# PulseGen.net
KiCad netlist of a schematic drawn in EAGLE
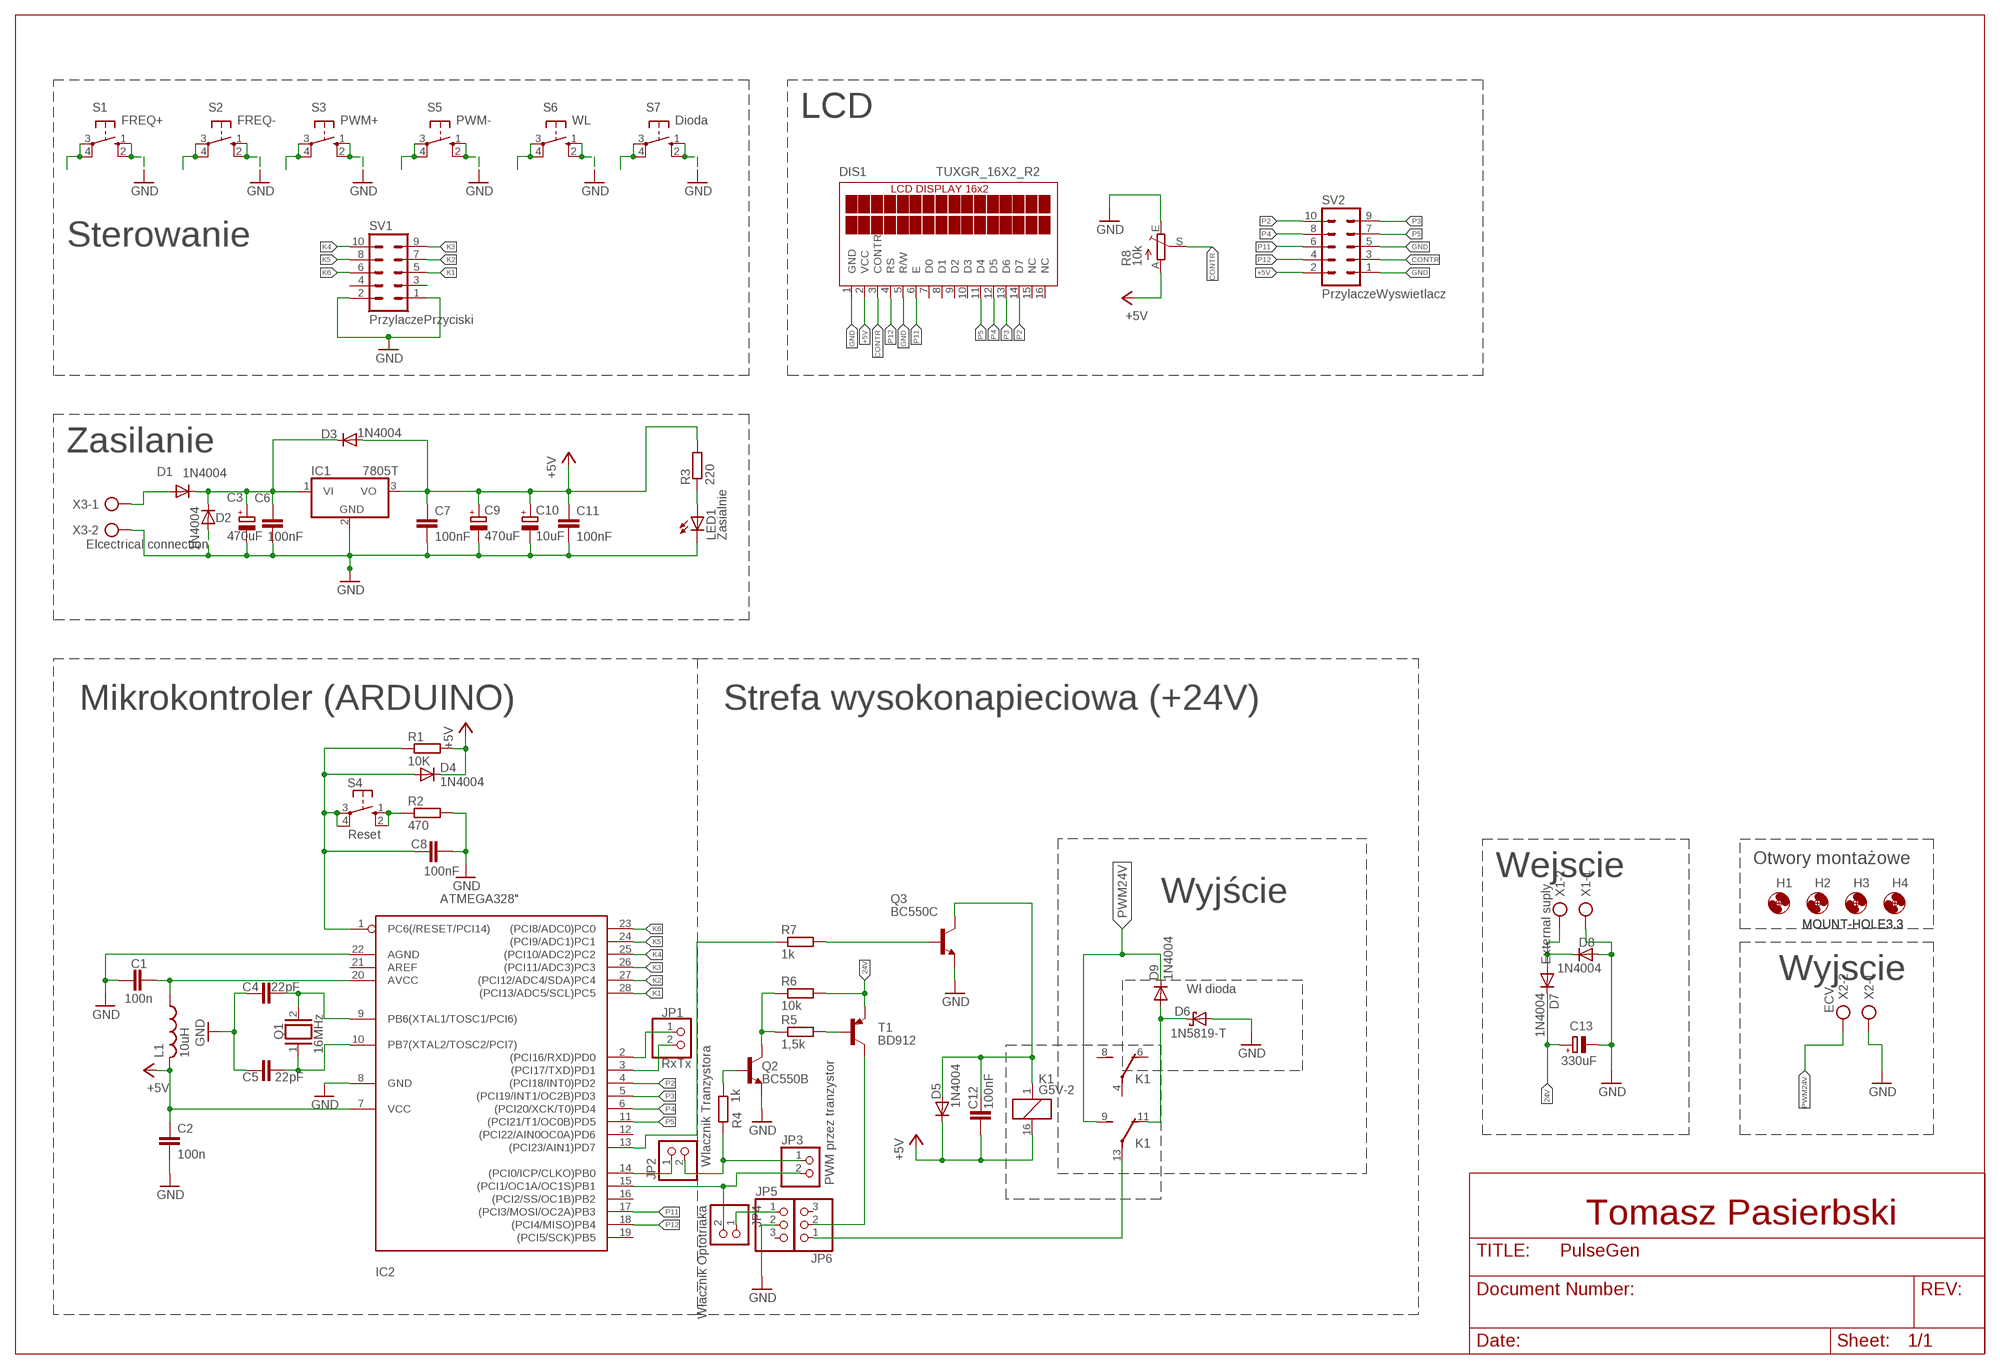
[diagram p0: schematic, sheet 1]

(export (version "E")
  (design (tool "Eeschema 10.0.6"))
  (components
    (comp (ref "C1")
      (value "100n")
      (footprint "eagle-import:C025-030X050")
      (libsource (lib "eagle-import") (part "C-EU025-030X050"))
    )
    (comp (ref "C2")
      (value "100n")
      (footprint "eagle-import:C025-030X050")
      (libsource (lib "eagle-import") (part "C-EU025-030X050"))
    )
    (comp (ref "C3")
      (value "470uF")
      (footprint "eagle-import:E3,5-8")
      (libsource (lib "eagle-import") (part "CPOL-EUE3.5-8"))
    )
    (comp (ref "C4")
      (value "22pF")
      (footprint "eagle-import:C025-024X044")
      (libsource (lib "eagle-import") (part "C-EU025-024X044"))
    )
    (comp (ref "C5")
      (value "22pF")
      (footprint "eagle-import:C025-024X044")
      (libsource (lib "eagle-import") (part "C-EU025-024X044"))
    )
    (comp (ref "C6")
      (value "100nF")
      (footprint "eagle-import:C025-030X050")
      (libsource (lib "eagle-import") (part "C-EU025-030X050"))
    )
    (comp (ref "C7")
      (value "100nF")
      (footprint "eagle-import:C025-030X050")
      (libsource (lib "eagle-import") (part "C-EU025-030X050"))
    )
    (comp (ref "C8")
      (value "100nF")
      (footprint "eagle-import:C025-030X050")
      (libsource (lib "eagle-import") (part "C-EU025-030X050"))
    )
    (comp (ref "C9")
      (value "470uF")
      (footprint "eagle-import:E3,5-8")
      (libsource (lib "eagle-import") (part "CPOL-EUE3.5-8"))
    )
    (comp (ref "C10")
      (value "10uF")
      (footprint "eagle-import:E5-6")
      (libsource (lib "eagle-import") (part "CPOL-EUE5-6"))
    )
    (comp (ref "C11")
      (value "100nF")
      (footprint "eagle-import:C025-030X050")
      (libsource (lib "eagle-import") (part "C-EU025-030X050"))
    )
    (comp (ref "C12")
      (value "100nF")
      (footprint "eagle-import:C025-030X050")
      (libsource (lib "eagle-import") (part "C-EU025-030X050"))
    )
    (comp (ref "C13")
      (value "330uF")
      (footprint "eagle-import:E7,5-18")
      (libsource (lib "eagle-import") (part "CPOL-EUE7.5-18"))
    )
    (comp (ref "D1")
      (value "1N4004")
      (footprint "eagle-import:DO41-10")
      (libsource (lib "eagle-import") (part "1N4004"))
    )
    (comp (ref "D2")
      (value "1N4004")
      (footprint "eagle-import:DO41-10")
      (libsource (lib "eagle-import") (part "1N4004"))
    )
    (comp (ref "D3")
      (value "1N4004")
      (footprint "eagle-import:DO41-10")
      (libsource (lib "eagle-import") (part "1N4004"))
    )
    (comp (ref "D4")
      (value "1N4004")
      (footprint "eagle-import:DO41-10")
      (libsource (lib "eagle-import") (part "1N4004"))
    )
    (comp (ref "D5")
      (value "1N4004")
      (footprint "eagle-import:DO41-10")
      (libsource (lib "eagle-import") (part "1N4004"))
    )
    (comp (ref "D6")
      (value "1N5819-T")
      (footprint "eagle-import:DO41-7.6")
      (libsource (lib "eagle-import") (part "1N5819-T"))
    )
    (comp (ref "D7")
      (value "1N4004")
      (footprint "eagle-import:DO41-10")
      (libsource (lib "eagle-import") (part "1N4004"))
    )
    (comp (ref "D8")
      (value "1N4004")
      (footprint "eagle-import:DO41-10")
      (libsource (lib "eagle-import") (part "1N4004"))
    )
    (comp (ref "D9")
      (value "1N4004")
      (footprint "eagle-import:DO41-10")
      (libsource (lib "eagle-import") (part "1N4004"))
    )
    (comp (ref "DIS1")
      (value "TUXGR_16X2_R2")
      (footprint "eagle-import:TUXGR_16X2_R2")
      (libsource (lib "eagle-import") (part "TUXGR_16X2_R2"))
    )
    (comp (ref "H1")
      (value "MOUNT-HOLE3.3")
      (footprint "eagle-import:3,3")
      (libsource (lib "eagle-import") (part "MOUNT-HOLE3.3"))
    )
    (comp (ref "H2")
      (value "MOUNT-HOLE3.3")
      (footprint "eagle-import:3,3")
      (libsource (lib "eagle-import") (part "MOUNT-HOLE3.3"))
    )
    (comp (ref "H3")
      (value "MOUNT-HOLE3.3")
      (footprint "eagle-import:3,3")
      (libsource (lib "eagle-import") (part "MOUNT-HOLE3.3"))
    )
    (comp (ref "H4")
      (value "MOUNT-HOLE3.3")
      (footprint "eagle-import:3,3")
      (libsource (lib "eagle-import") (part "MOUNT-HOLE3.3"))
    )
    (comp (ref "IC1")
      (value "7805T")
      (footprint "eagle-import:TO220H")
      (libsource (lib "eagle-import") (part "78T05"))
    )
    (comp (ref "IC2")
      (value "ATMEGA328\"")
      (footprint "eagle-import:ATMEGA328")
      (libsource (lib "eagle-import") (part "ATMEGA328{dblquote}"))
    )
    (comp (ref "JP1")
      (value "RxTx")
      (footprint "eagle-import:1X02")
      (libsource (lib "eagle-import") (part "PINHD-1X2"))
    )
    (comp (ref "JP2")
      (value "Wlacznik Tranzystora")
      (footprint "eagle-import:1X02")
      (libsource (lib "eagle-import") (part "PINHD-1X2"))
    )
    (comp (ref "JP3")
      (value "PWM przez tranzystor")
      (footprint "eagle-import:1X02")
      (libsource (lib "eagle-import") (part "PINHD-1X2"))
    )
    (comp (ref "JP4")
      (value "Włacznik Optotriaka")
      (footprint "eagle-import:1X02")
      (libsource (lib "eagle-import") (part "PINHD-1X2"))
    )
    (comp (ref "JP5")
      (value "PINHD-1X3")
      (footprint "eagle-import:1X03")
      (libsource (lib "eagle-import") (part "PINHD-1X3"))
    )
    (comp (ref "JP6")
      (value "PINHD-1X3")
      (footprint "eagle-import:1X03")
      (libsource (lib "eagle-import") (part "PINHD-1X3"))
    )
    (comp (ref "K1")
      (value "G5V-2")
      (footprint "eagle-import:G5V-2")
      (fields (field (name "MPN") "G5V-2 5DC"))
      (libsource (lib "eagle-import") (part "G5V-2"))
    )
    (comp (ref "L1")
      (value "10uH")
      (footprint "eagle-import:0204_7")
      (libsource (lib "eagle-import") (part "L-US0204/7"))
    )
    (comp (ref "LED1")
      (value "Zasialnie")
      (footprint "eagle-import:LED5MM")
      (libsource (lib "eagle-import") (part "LED5MM"))
    )
    (comp (ref "Q1")
      (value "16MHz")
      (footprint "eagle-import:QS")
      (libsource (lib "eagle-import") (part "XTAL/S"))
    )
    (comp (ref "Q2")
      (value "BC550B")
      (footprint "eagle-import:TO92-EBC")
      (libsource (lib "eagle-import") (part "BC550B"))
    )
    (comp (ref "Q3")
      (value "BC550C")
      (footprint "eagle-import:TO92-EBC")
      (libsource (lib "eagle-import") (part "BC550C"))
    )
    (comp (ref "R1")
      (value "10K")
      (footprint "eagle-import:0207_2V")
      (libsource (lib "eagle-import") (part "R-EU_0207/2V"))
    )
    (comp (ref "R2")
      (value "470")
      (footprint "eagle-import:0207_2V")
      (libsource (lib "eagle-import") (part "R-EU_0207/2V"))
    )
    (comp (ref "R3")
      (value "220")
      (footprint "eagle-import:0204_7")
      (libsource (lib "eagle-import") (part "R-EU_0204/7"))
    )
    (comp (ref "R4")
      (value "1k")
      (footprint "eagle-import:0204_7")
      (libsource (lib "eagle-import") (part "R-EU_0204/7"))
    )
    (comp (ref "R5")
      (value "1,5k")
      (footprint "eagle-import:0207_12")
      (libsource (lib "eagle-import") (part "R-EU_0207/12"))
    )
    (comp (ref "R6")
      (value "10k")
      (footprint "eagle-import:0204_7")
      (libsource (lib "eagle-import") (part "R-EU_0204/7"))
    )
    (comp (ref "R7")
      (value "1k")
      (footprint "eagle-import:0204_7")
      (libsource (lib "eagle-import") (part "R-EU_0204/7"))
    )
    (comp (ref "R8")
      (value "10k")
      (footprint "eagle-import:CA6V")
      (libsource (lib "eagle-import") (part "TRIM_EU-CA6V"))
    )
    (comp (ref "S1")
      (value "FREQ+")
      (footprint "eagle-import:B3F-10XX")
      (fields (field (name "MPN") "B3F-1000"))
      (libsource (lib "eagle-import") (part "10-XX"))
    )
    (comp (ref "S2")
      (value "FREQ-")
      (footprint "eagle-import:B3F-10XX")
      (fields (field (name "MPN") "B3F-1000"))
      (libsource (lib "eagle-import") (part "10-XX"))
    )
    (comp (ref "S3")
      (value "PWM+")
      (footprint "eagle-import:B3F-10XX")
      (fields (field (name "MPN") "B3F-1000"))
      (libsource (lib "eagle-import") (part "10-XX"))
    )
    (comp (ref "S4")
      (value "Reset")
      (footprint "eagle-import:B3F-10XX")
      (fields (field (name "MPN") "B3F-1000"))
      (libsource (lib "eagle-import") (part "10-XX"))
    )
    (comp (ref "S5")
      (value "PWM-")
      (footprint "eagle-import:B3F-10XX")
      (fields (field (name "MPN") "B3F-1000"))
      (libsource (lib "eagle-import") (part "10-XX"))
    )
    (comp (ref "S6")
      (value "WL")
      (footprint "eagle-import:B3F-10XX")
      (fields (field (name "MPN") "B3F-1000"))
      (libsource (lib "eagle-import") (part "10-XX"))
    )
    (comp (ref "S7")
      (value "Dioda")
      (footprint "eagle-import:B3F-10XX")
      (fields (field (name "MPN") "B3F-1000"))
      (libsource (lib "eagle-import") (part "10-XX"))
    )
    (comp (ref "SV1")
      (value "PrzylaczePrzyciski")
      (footprint "eagle-import:ML10")
      (libsource (lib "eagle-import") (part "ML10"))
    )
    (comp (ref "SV2")
      (value "PrzylaczeWyswietlacz")
      (footprint "eagle-import:ML10")
      (libsource (lib "eagle-import") (part "ML10"))
    )
    (comp (ref "T1")
      (value "BD912")
      (footprint "eagle-import:TO220")
      (libsource (lib "eagle-import") (part "TIP32"))
    )
    (comp (ref "X1")
      (value "External suply")
      (footprint "eagle-import:AK300_2")
      (libsource (lib "eagle-import") (part "AK300/2"))
    )
    (comp (ref "X2")
      (value "ECV")
      (footprint "eagle-import:AK300_2")
      (libsource (lib "eagle-import") (part "AK300/2"))
    )
    (comp (ref "X3")
      (value "Elcectrical connection")
      (footprint "eagle-import:AK300_2")
      (libsource (lib "eagle-import") (part "AK300/2"))
    )
  )
  (nets
    (net (code "1") (name "+5V") (class "Default")
      (node (ref "C10") (pin "+") (pinfunction "+_+") (pintype "passive"))
      (node (ref "C11") (pin "1") (pinfunction "1_1") (pintype "passive"))
      (node (ref "C12") (pin "2") (pinfunction "2_2") (pintype "passive"))
      (node (ref "C2") (pin "1") (pinfunction "1_1") (pintype "passive"))
      (node (ref "C7") (pin "1") (pinfunction "1_1") (pintype "passive"))
      (node (ref "C9") (pin "+") (pinfunction "+_+") (pintype "passive"))
      (node (ref "D3") (pin "A") (pinfunction "A_A") (pintype "passive"))
      (node (ref "D4") (pin "C") (pinfunction "C_C") (pintype "passive"))
      (node (ref "D5") (pin "C") (pinfunction "C_C") (pintype "passive"))
      (node (ref "DIS1") (pin "2") (pinfunction "VCC_2") (pintype "power_in"))
      (node (ref "IC1") (pin "3") (pinfunction "VO_3") (pintype "passive"))
      (node (ref "IC2") (pin "7") (pinfunction "VCC_7") (pintype "bidirectional"))
      (node (ref "K1") (pin "16") (pinfunction "2_16") (pintype "passive"))
      (node (ref "L1") (pin "2") (pinfunction "2_2") (pintype "passive"))
      (node (ref "R1") (pin "2") (pinfunction "2_2") (pintype "passive"))
      (node (ref "R3") (pin "2") (pinfunction "2_2") (pintype "passive"))
      (node (ref "R8") (pin "A") (pinfunction "A_A") (pintype "passive"))
      (node (ref "SV2") (pin "2") (pinfunction "2_2") (pintype "passive"))
    )
    (net (code "2") (name "24V") (class "Default")
      (node (ref "C13") (pin "+") (pinfunction "+_+") (pintype "passive"))
      (node (ref "D7") (pin "C") (pinfunction "C_C") (pintype "passive"))
      (node (ref "R6") (pin "2") (pinfunction "2_2") (pintype "passive"))
      (node (ref "T1") (pin "3") (pinfunction "E_3") (pintype "passive"))
    )
    (net (code "3") (name "CONTR") (class "Default")
      (node (ref "DIS1") (pin "3") (pinfunction "CONTR_3") (pintype "input"))
      (node (ref "R8") (pin "S") (pinfunction "S_S") (pintype "passive"))
      (node (ref "SV2") (pin "3") (pinfunction "3_3") (pintype "passive"))
    )
    (net (code "4") (name "GND") (class "Default")
      (node (ref "C1") (pin "2") (pinfunction "2_2") (pintype "passive"))
      (node (ref "C10") (pin "-") (pinfunction "-_-") (pintype "passive"))
      (node (ref "C11") (pin "2") (pinfunction "2_2") (pintype "passive"))
      (node (ref "C13") (pin "-") (pinfunction "-_-") (pintype "passive"))
      (node (ref "C2") (pin "2") (pinfunction "2_2") (pintype "passive"))
      (node (ref "C3") (pin "-") (pinfunction "-_-") (pintype "passive"))
      (node (ref "C4") (pin "1") (pinfunction "1_1") (pintype "passive"))
      (node (ref "C5") (pin "1") (pinfunction "1_1") (pintype "passive"))
      (node (ref "C6") (pin "2") (pinfunction "2_2") (pintype "passive"))
      (node (ref "C7") (pin "2") (pinfunction "2_2") (pintype "passive"))
      (node (ref "C8") (pin "2") (pinfunction "2_2") (pintype "passive"))
      (node (ref "C9") (pin "-") (pinfunction "-_-") (pintype "passive"))
      (node (ref "D2") (pin "A") (pinfunction "A_A") (pintype "passive"))
      (node (ref "D6") (pin "A") (pinfunction "A_A") (pintype "passive"))
      (node (ref "D8") (pin "A") (pinfunction "A_A") (pintype "passive"))
      (node (ref "DIS1") (pin "1") (pinfunction "GND_1") (pintype "power_in"))
      (node (ref "DIS1") (pin "5") (pinfunction "R/W_5") (pintype "input"))
      (node (ref "IC1") (pin "2") (pinfunction "GND_2") (pintype "passive"))
      (node (ref "IC2") (pin "22") (pinfunction "AGND_22") (pintype "bidirectional"))
      (node (ref "IC2") (pin "8") (pinfunction "GND_8") (pintype "bidirectional"))
      (node (ref "JP5") (pin "2") (pinfunction "2_2") (pintype "passive"))
      (node (ref "LED1") (pin "K") (pinfunction "C_K") (pintype "passive"))
      (node (ref "Q2") (pin "E") (pinfunction "E_E") (pintype "passive"))
      (node (ref "Q3") (pin "E") (pinfunction "E_E") (pintype "passive"))
      (node (ref "R2") (pin "2") (pinfunction "2_2") (pintype "passive"))
      (node (ref "R8") (pin "E") (pinfunction "E_E") (pintype "passive"))
      (node (ref "S1") (pin "1") (pinfunction "S_1") (pintype "passive"))
      (node (ref "S1") (pin "2") (pinfunction "S1_2") (pintype "passive"))
      (node (ref "S2") (pin "1") (pinfunction "S_1") (pintype "passive"))
      (node (ref "S2") (pin "2") (pinfunction "S1_2") (pintype "passive"))
      (node (ref "S3") (pin "1") (pinfunction "S_1") (pintype "passive"))
      (node (ref "S3") (pin "2") (pinfunction "S1_2") (pintype "passive"))
      (node (ref "S5") (pin "1") (pinfunction "S_1") (pintype "passive"))
      (node (ref "S5") (pin "2") (pinfunction "S1_2") (pintype "passive"))
      (node (ref "S6") (pin "1") (pinfunction "S_1") (pintype "passive"))
      (node (ref "S6") (pin "2") (pinfunction "S1_2") (pintype "passive"))
      (node (ref "S7") (pin "1") (pinfunction "S_1") (pintype "passive"))
      (node (ref "S7") (pin "2") (pinfunction "S1_2") (pintype "passive"))
      (node (ref "SV1") (pin "1") (pinfunction "1_1") (pintype "passive"))
      (node (ref "SV1") (pin "2") (pinfunction "2_2") (pintype "passive"))
      (node (ref "SV2") (pin "1") (pinfunction "1_1") (pintype "passive"))
      (node (ref "SV2") (pin "5") (pinfunction "5_5") (pintype "passive"))
      (node (ref "X1") (pin "1") (pinfunction "KL_1") (pintype "passive"))
      (node (ref "X2") (pin "1") (pinfunction "KL_1") (pintype "passive"))
      (node (ref "X3") (pin "2") (pinfunction "KL_2") (pintype "passive"))
    )
    (net (code "5") (name "K1") (class "Default")
      (node (ref "IC2") (pin "28") (pinfunction "(PCI13/ADC5/SCL)PC5_28") (pintype "bidirectional"))
      (node (ref "SV1") (pin "5") (pinfunction "5_5") (pintype "passive"))
    )
    (net (code "6") (name "K2") (class "Default")
      (node (ref "IC2") (pin "27") (pinfunction "(PCI12/ADC4/SDA)PC4_27") (pintype "bidirectional"))
      (node (ref "SV1") (pin "7") (pinfunction "7_7") (pintype "passive"))
    )
    (net (code "7") (name "K3") (class "Default")
      (node (ref "IC2") (pin "26") (pinfunction "(PCI11/ADC3)PC3_26") (pintype "bidirectional"))
      (node (ref "SV1") (pin "9") (pinfunction "9_9") (pintype "passive"))
    )
    (net (code "8") (name "K4") (class "Default")
      (node (ref "IC2") (pin "25") (pinfunction "(PCI10/ADC2)PC2_25") (pintype "bidirectional"))
      (node (ref "SV1") (pin "10") (pinfunction "10_10") (pintype "passive"))
    )
    (net (code "9") (name "K5") (class "Default")
      (node (ref "IC2") (pin "24") (pinfunction "(PCI9/ADC1)PC1_24") (pintype "bidirectional"))
      (node (ref "SV1") (pin "8") (pinfunction "8_8") (pintype "passive"))
    )
    (net (code "10") (name "K6") (class "Default")
      (node (ref "IC2") (pin "23") (pinfunction "(PCI8/ADC0)PC0_23") (pintype "bidirectional"))
      (node (ref "SV1") (pin "6") (pinfunction "6_6") (pintype "passive"))
    )
    (net (code "11") (name "Net-(C12-Pad1)") (class "Default")
      (node (ref "C12") (pin "1") (pinfunction "1_1") (pintype "passive"))
      (node (ref "D5") (pin "A") (pinfunction "A_A") (pintype "passive"))
      (node (ref "K1") (pin "1") (pinfunction "1_1") (pintype "passive"))
      (node (ref "Q3") (pin "C") (pinfunction "C_C") (pintype "passive"))
    )
    (net (code "12") (name "Net-(IC1-VI)") (class "Default")
      (node (ref "C3") (pin "+") (pinfunction "+_+") (pintype "passive"))
      (node (ref "C6") (pin "1") (pinfunction "1_1") (pintype "passive"))
      (node (ref "D1") (pin "C") (pinfunction "C_C") (pintype "passive"))
      (node (ref "D2") (pin "C") (pinfunction "C_C") (pintype "passive"))
      (node (ref "D3") (pin "C") (pinfunction "C_C") (pintype "passive"))
      (node (ref "IC1") (pin "1") (pinfunction "VI_1") (pintype "input"))
    )
    (net (code "13") (name "Net-(IC2-(PCI0{slash}ICP{slash}CLKO)PB0)") (class "Default")
      (node (ref "IC2") (pin "14") (pinfunction "(PCI0/ICP/CLKO)PB0_14") (pintype "bidirectional"))
      (node (ref "JP2") (pin "1") (pinfunction "1_1") (pintype "passive"))
    )
    (net (code "14") (name "Net-(IC2-(PCI1{slash}OC1A{slash}OC1S)PB1)") (class "Default")
      (node (ref "IC2") (pin "15") (pinfunction "(PCI1/OC1A/OC1S)PB1_15") (pintype "bidirectional"))
      (node (ref "JP3") (pin "2") (pinfunction "2_2") (pintype "passive"))
      (node (ref "JP4") (pin "2") (pinfunction "2_2") (pintype "passive"))
    )
    (net (code "15") (name "Net-(IC2-(PCI16{slash}RXD)PD0)") (class "Default")
      (node (ref "IC2") (pin "2") (pinfunction "(PCI16/RXD)PD0_2") (pintype "bidirectional"))
      (node (ref "JP1") (pin "1") (pinfunction "1_1") (pintype "passive"))
    )
    (net (code "16") (name "Net-(IC2-(PCI17{slash}TXD)PD1)") (class "Default")
      (node (ref "IC2") (pin "3") (pinfunction "(PCI17/TXD)PD1_3") (pintype "bidirectional"))
      (node (ref "JP1") (pin "2") (pinfunction "2_2") (pintype "passive"))
    )
    (net (code "17") (name "Net-(IC2-(PCI23{slash}AIN1)PD7)") (class "Default")
      (node (ref "IC2") (pin "13") (pinfunction "(PCI23/AIN1)PD7_13") (pintype "bidirectional"))
      (node (ref "R7") (pin "1") (pinfunction "1_1") (pintype "passive"))
    )
    (net (code "18") (name "Net-(IC2-AVCC)") (class "Default")
      (node (ref "C1") (pin "1") (pinfunction "1_1") (pintype "passive"))
      (node (ref "IC2") (pin "20") (pinfunction "AVCC_20") (pintype "bidirectional"))
      (node (ref "L1") (pin "1") (pinfunction "1_1") (pintype "passive"))
    )
    (net (code "19") (name "Net-(IC2-PB6(XTAL1{slash}TOSC1{slash}PCI6))") (class "Default")
      (node (ref "C4") (pin "2") (pinfunction "2_2") (pintype "passive"))
      (node (ref "IC2") (pin "9") (pinfunction "PB6(XTAL1/TOSC1/PCI6)_9") (pintype "bidirectional"))
      (node (ref "Q1") (pin "2") (pinfunction "2_2") (pintype "passive"))
    )
    (net (code "20") (name "Net-(IC2-PB7(XTAL2{slash}TOSC2{slash}PCI7))") (class "Default")
      (node (ref "C5") (pin "2") (pinfunction "2_2") (pintype "passive"))
      (node (ref "IC2") (pin "10") (pinfunction "PB7(XTAL2/TOSC2/PCI7)_10") (pintype "bidirectional"))
      (node (ref "Q1") (pin "1") (pinfunction "1_1") (pintype "passive"))
    )
    (net (code "21") (name "Net-(IC2-PC6({slash}RESET{slash}PCI14))") (class "Default")
      (node (ref "C8") (pin "1") (pinfunction "1_1") (pintype "passive"))
      (node (ref "D4") (pin "A") (pinfunction "A_A") (pintype "passive"))
      (node (ref "IC2") (pin "1") (pinfunction "PC6(/RESET/PCI14)_1") (pintype "bidirectional"))
      (node (ref "R1") (pin "1") (pinfunction "1_1") (pintype "passive"))
      (node (ref "S4") (pin "3") (pinfunction "P_3") (pintype "passive"))
      (node (ref "S4") (pin "4") (pinfunction "P1_4") (pintype "passive"))
    )
    (net (code "22") (name "Net-(JP2-Pad2)") (class "Default")
      (node (ref "JP2") (pin "2") (pinfunction "2_2") (pintype "passive"))
      (node (ref "JP3") (pin "1") (pinfunction "1_1") (pintype "passive"))
      (node (ref "R4") (pin "1") (pinfunction "1_1") (pintype "passive"))
    )
    (net (code "23") (name "Net-(JP4-Pad1)") (class "Default")
      (node (ref "JP4") (pin "1") (pinfunction "1_1") (pintype "passive"))
      (node (ref "JP5") (pin "1") (pinfunction "1_1") (pintype "passive"))
    )
    (net (code "24") (name "Net-(K1B-O)") (class "Default")
      (node (ref "D6") (pin "C") (pinfunction "C_C") (pintype "passive"))
      (node (ref "D9") (pin "A") (pinfunction "A_A") (pintype "passive"))
      (node (ref "K1") (pin "11") (pinfunction "O_11") (pintype "passive"))
    )
    (net (code "25") (name "Net-(K1B-P)") (class "Default")
      (node (ref "JP6") (pin "1") (pinfunction "1_1") (pintype "passive"))
      (node (ref "K1") (pin "13") (pinfunction "P_13") (pintype "passive"))
    )
    (net (code "26") (name "Net-(LED1-PadA)") (class "Default")
      (node (ref "LED1") (pin "A") (pinfunction "A_A") (pintype "passive"))
      (node (ref "R3") (pin "1") (pinfunction "1_1") (pintype "passive"))
    )
    (net (code "27") (name "Net-(Q2-PadB)") (class "Default")
      (node (ref "Q2") (pin "B") (pinfunction "B_B") (pintype "passive"))
      (node (ref "R4") (pin "2") (pinfunction "2_2") (pintype "passive"))
    )
    (net (code "28") (name "Net-(Q2-PadC)") (class "Default")
      (node (ref "Q2") (pin "C") (pinfunction "C_C") (pintype "passive"))
      (node (ref "R5") (pin "1") (pinfunction "1_1") (pintype "passive"))
      (node (ref "R6") (pin "1") (pinfunction "1_1") (pintype "passive"))
    )
    (net (code "29") (name "Net-(Q3-PadB)") (class "Default")
      (node (ref "Q3") (pin "B") (pinfunction "B_B") (pintype "passive"))
      (node (ref "R7") (pin "2") (pinfunction "2_2") (pintype "passive"))
    )
    (net (code "30") (name "Net-(S1-P)") (class "Default")
      (node (ref "S1") (pin "3") (pinfunction "P_3") (pintype "passive"))
      (node (ref "S1") (pin "4") (pinfunction "P1_4") (pintype "passive"))
    )
    (net (code "31") (name "Net-(S2-P)") (class "Default")
      (node (ref "S2") (pin "3") (pinfunction "P_3") (pintype "passive"))
      (node (ref "S2") (pin "4") (pinfunction "P1_4") (pintype "passive"))
    )
    (net (code "32") (name "Net-(S3-P)") (class "Default")
      (node (ref "S3") (pin "3") (pinfunction "P_3") (pintype "passive"))
      (node (ref "S3") (pin "4") (pinfunction "P1_4") (pintype "passive"))
    )
    (net (code "33") (name "Net-(S4-S)") (class "Default")
      (node (ref "R2") (pin "1") (pinfunction "1_1") (pintype "passive"))
      (node (ref "S4") (pin "1") (pinfunction "S_1") (pintype "passive"))
      (node (ref "S4") (pin "2") (pinfunction "S1_2") (pintype "passive"))
    )
    (net (code "34") (name "Net-(S5-P)") (class "Default")
      (node (ref "S5") (pin "3") (pinfunction "P_3") (pintype "passive"))
      (node (ref "S5") (pin "4") (pinfunction "P1_4") (pintype "passive"))
    )
    (net (code "35") (name "Net-(S6-P)") (class "Default")
      (node (ref "S6") (pin "3") (pinfunction "P_3") (pintype "passive"))
      (node (ref "S6") (pin "4") (pinfunction "P1_4") (pintype "passive"))
    )
    (net (code "36") (name "Net-(S7-P)") (class "Default")
      (node (ref "S7") (pin "3") (pinfunction "P_3") (pintype "passive"))
      (node (ref "S7") (pin "4") (pinfunction "P1_4") (pintype "passive"))
    )
    (net (code "37") (name "Net-(T1-B)") (class "Default")
      (node (ref "R5") (pin "2") (pinfunction "2_2") (pintype "passive"))
      (node (ref "T1") (pin "1") (pinfunction "B_1") (pintype "passive"))
    )
    (net (code "38") (name "Net-(T1-C)") (class "Default")
      (node (ref "JP6") (pin "2") (pinfunction "2_2") (pintype "passive"))
      (node (ref "T1") (pin "2") (pinfunction "C_2") (pintype "passive"))
    )
    (net (code "39") (name "Net-(X1B-KL)") (class "Default")
      (node (ref "D7") (pin "A") (pinfunction "A_A") (pintype "passive"))
      (node (ref "D8") (pin "C") (pinfunction "C_C") (pintype "passive"))
      (node (ref "X1") (pin "2") (pinfunction "KL_2") (pintype "passive"))
    )
    (net (code "40") (name "Net-(X3A-KL)") (class "Default")
      (node (ref "D1") (pin "A") (pinfunction "A_A") (pintype "passive"))
      (node (ref "X3") (pin "1") (pinfunction "KL_1") (pintype "passive"))
    )
    (net (code "41") (name "P2") (class "Default")
      (node (ref "DIS1") (pin "14") (pinfunction "D7_14") (pintype "input"))
      (node (ref "IC2") (pin "4") (pinfunction "(PCI18/INT0)PD2_4") (pintype "bidirectional"))
      (node (ref "SV2") (pin "10") (pinfunction "10_10") (pintype "passive"))
    )
    (net (code "42") (name "P3") (class "Default")
      (node (ref "DIS1") (pin "13") (pinfunction "D6_13") (pintype "input"))
      (node (ref "IC2") (pin "5") (pinfunction "(PCI19/INT1/OC2B)PD3_5") (pintype "bidirectional"))
      (node (ref "SV2") (pin "9") (pinfunction "9_9") (pintype "passive"))
    )
    (net (code "43") (name "P4") (class "Default")
      (node (ref "DIS1") (pin "12") (pinfunction "D5_12") (pintype "input"))
      (node (ref "IC2") (pin "6") (pinfunction "(PCI20/XCK/T0)PD4_6") (pintype "bidirectional"))
      (node (ref "SV2") (pin "8") (pinfunction "8_8") (pintype "passive"))
    )
    (net (code "44") (name "P5") (class "Default")
      (node (ref "DIS1") (pin "11") (pinfunction "D4_11") (pintype "input"))
      (node (ref "IC2") (pin "11") (pinfunction "(PCI21/T1/OC0B)PD5_11") (pintype "bidirectional"))
      (node (ref "SV2") (pin "7") (pinfunction "7_7") (pintype "passive"))
    )
    (net (code "45") (name "P11") (class "Default")
      (node (ref "DIS1") (pin "6") (pinfunction "E_6") (pintype "input"))
      (node (ref "IC2") (pin "17") (pinfunction "(PCI3/MOSI/OC2A)PB3_17") (pintype "bidirectional"))
      (node (ref "SV2") (pin "6") (pinfunction "6_6") (pintype "passive"))
    )
    (net (code "46") (name "P12") (class "Default")
      (node (ref "DIS1") (pin "4") (pinfunction "RS_4") (pintype "input"))
      (node (ref "IC2") (pin "18") (pinfunction "(PCI4/MISO)PB4_18") (pintype "bidirectional"))
      (node (ref "SV2") (pin "4") (pinfunction "4_4") (pintype "passive"))
    )
    (net (code "47") (name "PWM24V") (class "Default")
      (node (ref "D9") (pin "C") (pinfunction "C_C") (pintype "passive"))
      (node (ref "K1") (pin "9") (pinfunction "S_9") (pintype "passive"))
      (node (ref "X2") (pin "2") (pinfunction "KL_2") (pintype "passive"))
    )
    (net (code "48") (name "unconnected-(DIS1-D0-Pad7)") (class "Default")
      (node (ref "DIS1") (pin "7") (pinfunction "D0_7") (pintype "input"))
    )
    (net (code "49") (name "unconnected-(DIS1-D1-Pad8)") (class "Default")
      (node (ref "DIS1") (pin "8") (pinfunction "D1_8") (pintype "input"))
    )
    (net (code "50") (name "unconnected-(DIS1-D2-Pad9)") (class "Default")
      (node (ref "DIS1") (pin "9") (pinfunction "D2_9") (pintype "input"))
    )
    (net (code "51") (name "unconnected-(DIS1-D3-Pad10)") (class "Default")
      (node (ref "DIS1") (pin "10") (pinfunction "D3_10") (pintype "input"))
    )
    (net (code "52") (name "unconnected-(DIS1-NC-Pad15)") (class "Default")
      (node (ref "DIS1") (pin "15") (pinfunction "NC_15") (pintype "no_connect"))
    )
    (net (code "53") (name "unconnected-(DIS1-NC-Pad16)") (class "Default")
      (node (ref "DIS1") (pin "16") (pinfunction "NC_16") (pintype "no_connect"))
    )
    (net (code "54") (name "unconnected-(IC2-(PCI2{slash}SS{slash}OC1B)PB2-Pad16)") (class "Default")
      (node (ref "IC2") (pin "16") (pinfunction "(PCI2/SS/OC1B)PB2_16") (pintype "bidirectional"))
    )
    (net (code "55") (name "unconnected-(IC2-(PCI5{slash}SCK)PB5-Pad19)") (class "Default")
      (node (ref "IC2") (pin "19") (pinfunction "(PCI5/SCK)PB5_19") (pintype "bidirectional"))
    )
    (net (code "56") (name "unconnected-(IC2-(PCI22{slash}AIN0OC0A)PD6-Pad12)") (class "Default")
      (node (ref "IC2") (pin "12") (pinfunction "(PCI22/AIN0OC0A)PD6_12") (pintype "bidirectional"))
    )
    (net (code "57") (name "unconnected-(IC2-AREF-Pad21)") (class "Default")
      (node (ref "IC2") (pin "21") (pinfunction "AREF_21") (pintype "bidirectional"))
    )
    (net (code "58") (name "unconnected-(JP5-Pad3)") (class "Default")
      (node (ref "JP5") (pin "3") (pinfunction "3_3") (pintype "passive"))
    )
    (net (code "59") (name "unconnected-(JP6-Pad3)") (class "Default")
      (node (ref "JP6") (pin "3") (pinfunction "3_3") (pintype "passive"))
    )
    (net (code "60") (name "unconnected-(K1A-O-Pad6)") (class "Default")
      (node (ref "K1") (pin "6") (pinfunction "O_6") (pintype "passive"))
    )
    (net (code "61") (name "unconnected-(K1A-P-Pad4)") (class "Default")
      (node (ref "K1") (pin "4") (pinfunction "P_4") (pintype "passive"))
    )
    (net (code "62") (name "unconnected-(K1A-S-Pad8)") (class "Default")
      (node (ref "K1") (pin "8") (pinfunction "S_8") (pintype "passive"))
    )
    (net (code "63") (name "unconnected-(SV1-Pad3)") (class "Default")
      (node (ref "SV1") (pin "3") (pinfunction "3_3") (pintype "passive"))
    )
    (net (code "64") (name "unconnected-(SV1-Pad4)") (class "Default")
      (node (ref "SV1") (pin "4") (pinfunction "4_4") (pintype "passive"))
    )
  )
)
